# 03_-_HV_Input.net
KiCad netlist of a schematic drawn in Altium Designer
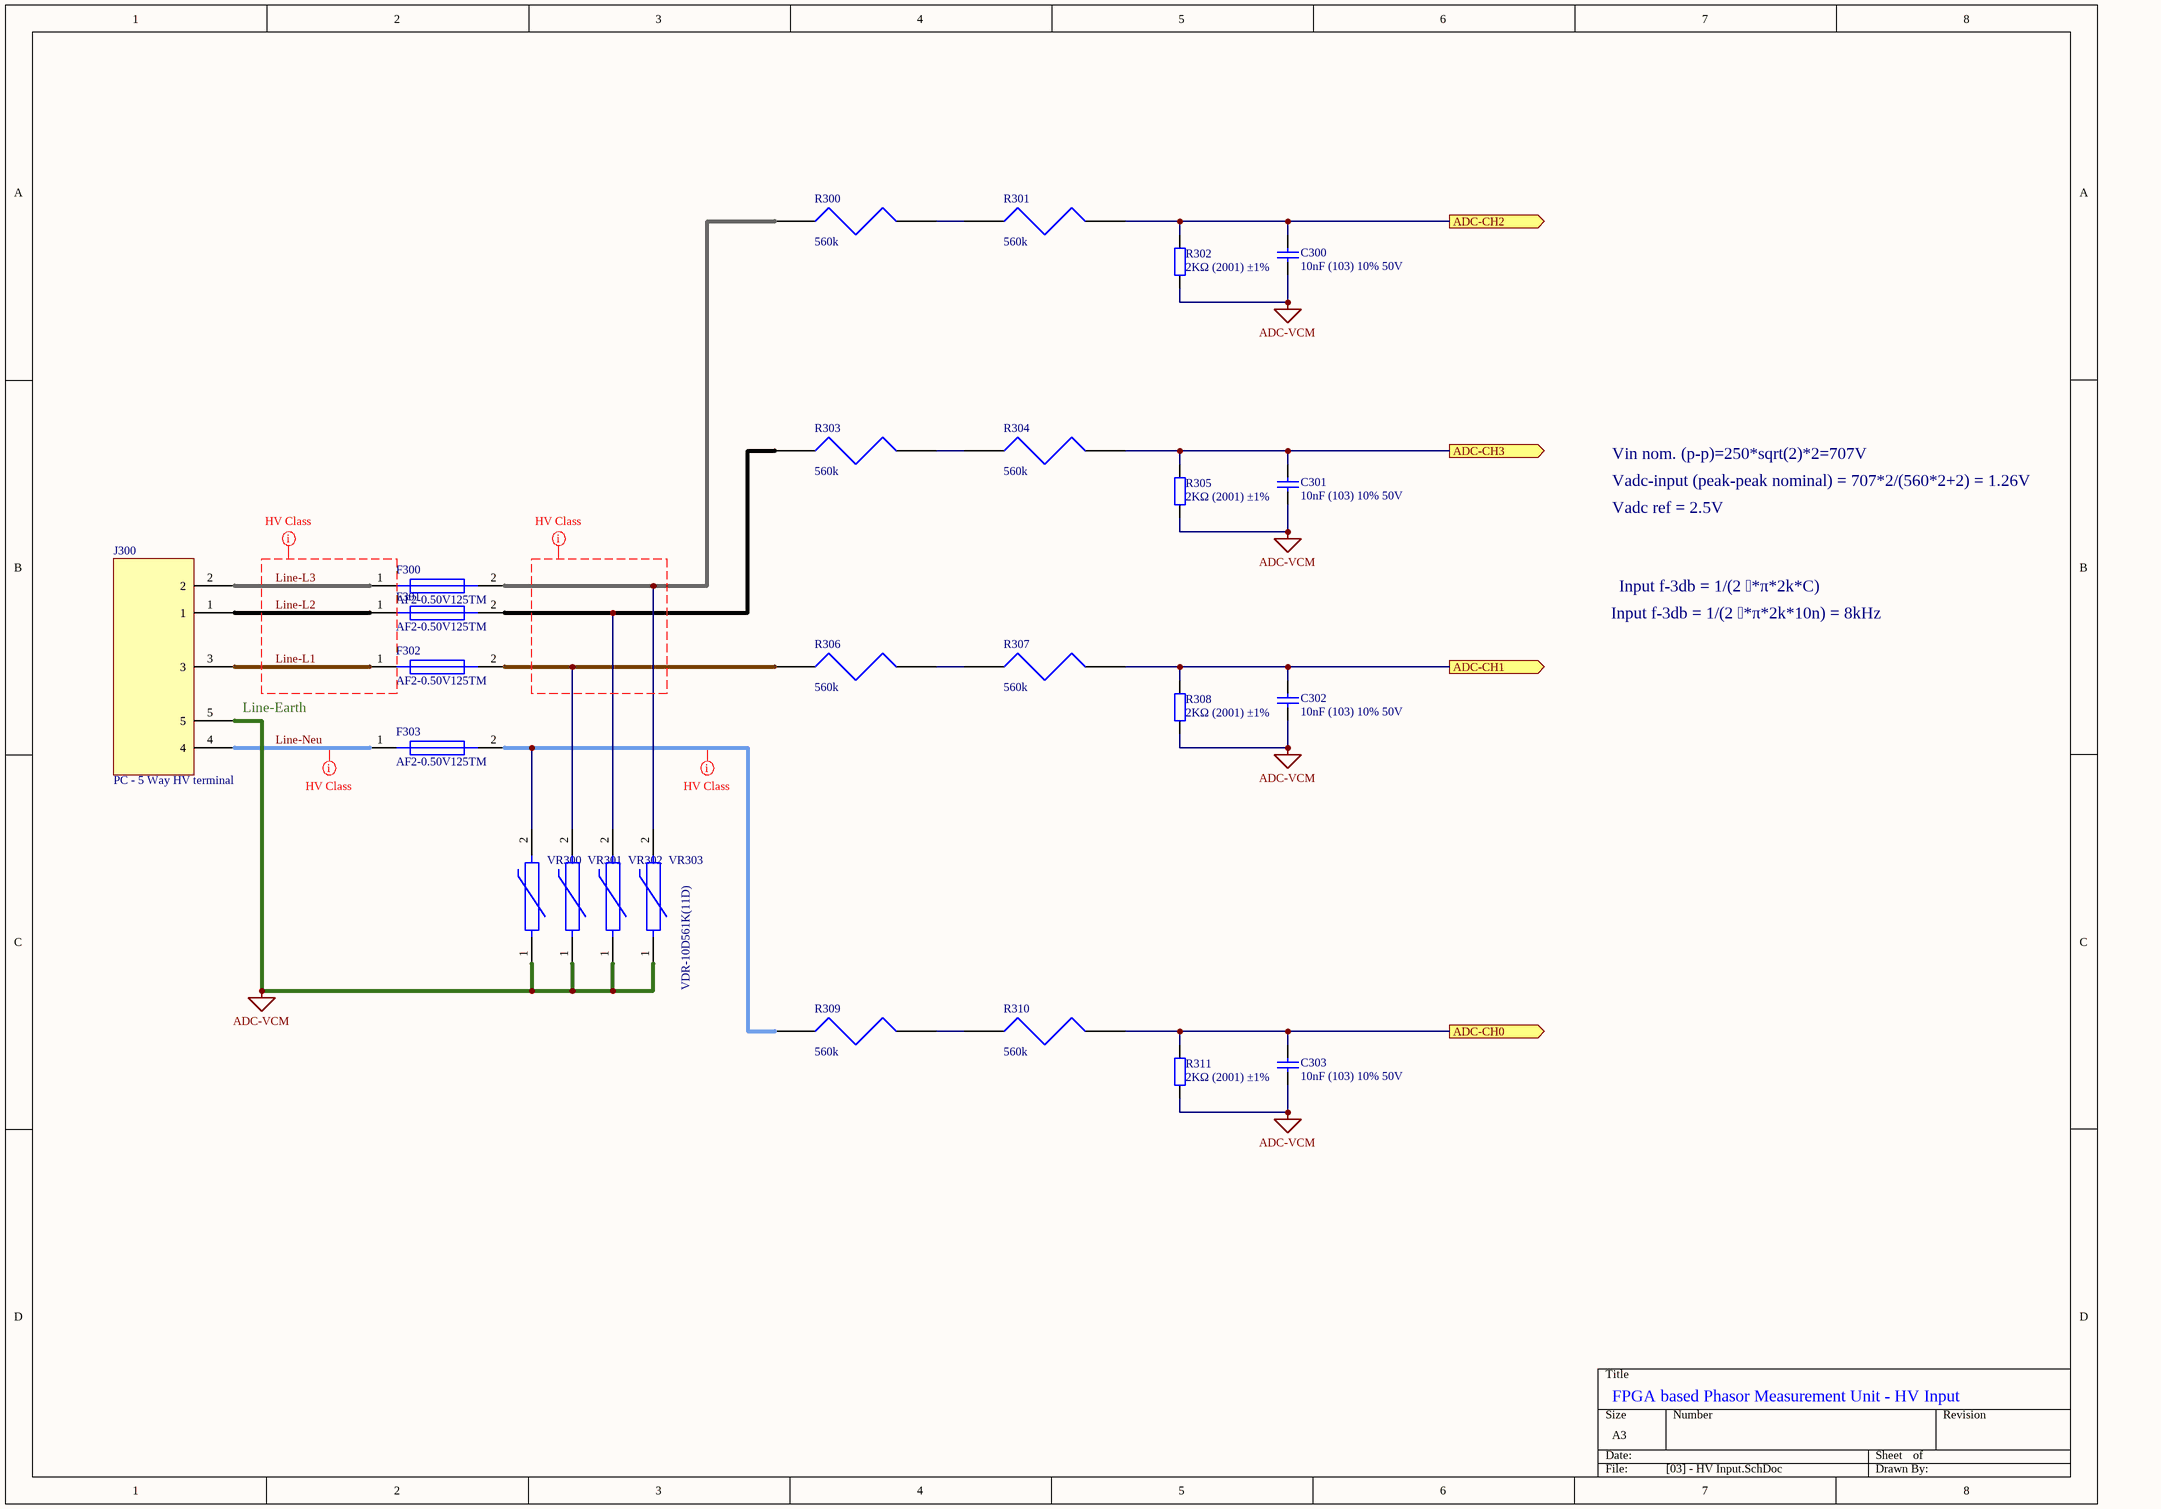
[diagram p0: [03] - HV Input.SchDoc]

(export (version "E")
  (design (tool "Eeschema 10.0.6"))
  (components
    (comp (ref "C300")
      (value "10nF (103) 10% 50V")
      (footprint "0805_C")
      (description "贴片电容")
      (libsource (lib "Cap") (part "0805 10nF (103) 10% 50V"))
    )
    (comp (ref "C301")
      (value "10nF (103) 10% 50V")
      (footprint "0805_C")
      (description "贴片电容")
      (libsource (lib "Cap") (part "0805 10nF (103) 10% 50V"))
    )
    (comp (ref "C302")
      (value "10nF (103) 10% 50V")
      (footprint "0805_C")
      (description "贴片电容")
      (libsource (lib "Cap") (part "0805 10nF (103) 10% 50V"))
    )
    (comp (ref "C303")
      (value "10nF (103) 10% 50V")
      (footprint "0805_C")
      (description "贴片电容")
      (libsource (lib "Cap") (part "0805 10nF (103) 10% 50V"))
    )
    (comp (ref "F300")
      (value "AF2-0.50V125TM")
      (footprint "2410 Fuse")
      (description "Chip Fuse Fast Blow 500mA 231mΩ 100A AC，50A DC 0.1 2410 Surface Mount Fuses RoHS")
      (libsource (lib "FPGA_PMU_lib") (part "AF2-0.50V125TM"))
    )
    (comp (ref "F301")
      (value "AF2-0.50V125TM")
      (footprint "2410 Fuse")
      (description "Chip Fuse Fast Blow 500mA 231mΩ 100A AC，50A DC 0.1 2410 Surface Mount Fuses RoHS")
      (libsource (lib "FPGA_PMU_lib") (part "AF2-0.50V125TM"))
    )
    (comp (ref "F302")
      (value "AF2-0.50V125TM")
      (footprint "2410 Fuse")
      (description "Chip Fuse Fast Blow 500mA 231mΩ 100A AC，50A DC 0.1 2410 Surface Mount Fuses RoHS")
      (libsource (lib "FPGA_PMU_lib") (part "AF2-0.50V125TM"))
    )
    (comp (ref "F303")
      (value "AF2-0.50V125TM")
      (footprint "2410 Fuse")
      (description "Chip Fuse Fast Blow 500mA 231mΩ 100A AC，50A DC 0.1 2410 Surface Mount Fuses RoHS")
      (libsource (lib "FPGA_PMU_lib") (part "AF2-0.50V125TM"))
    )
    (comp (ref "J300")
      (value "PC - 5 Way HV terminal")
      (footprint "1017517")
      (description "TDPT 4/ 5-SC-6,35-ZB - 1017517")
      (libsource (lib "FPGA_PMU_lib") (part "PC - 5 Way HV terminal"))
    )
    (comp (ref "R300")
      (value "560k")
      (footprint "FPGA_PMU_lib:2512_HV_RES")
      (description "HIGH VOLTAGE RESISTOR 560KOHMS ±1% 1W 2512 ROHS")
      (libsource (lib "FPGA_PMU_lib") (part "HR2512F560KE04Z"))
    )
    (comp (ref "R301")
      (value "560k")
      (footprint "FPGA_PMU_lib:2512_HV_RES")
      (description "HIGH VOLTAGE RESISTOR 560KOHMS ±1% 1W 2512 ROHS")
      (libsource (lib "FPGA_PMU_lib") (part "HR2512F560KE04Z"))
    )
    (comp (ref "R302")
      (value "2KΩ (2001) ±1%")
      (footprint "0805_R")
      (description "贴片电阻")
      (libsource (lib "RES") (part "0805 2KΩ (2001) 1%"))
    )
    (comp (ref "R303")
      (value "560k")
      (footprint "FPGA_PMU_lib:2512_HV_RES")
      (description "HIGH VOLTAGE RESISTOR 560KOHMS ±1% 1W 2512 ROHS")
      (libsource (lib "FPGA_PMU_lib") (part "HR2512F560KE04Z"))
    )
    (comp (ref "R304")
      (value "560k")
      (footprint "FPGA_PMU_lib:2512_HV_RES")
      (description "HIGH VOLTAGE RESISTOR 560KOHMS ±1% 1W 2512 ROHS")
      (libsource (lib "FPGA_PMU_lib") (part "HR2512F560KE04Z"))
    )
    (comp (ref "R305")
      (value "2KΩ (2001) ±1%")
      (footprint "0805_R")
      (description "贴片电阻")
      (libsource (lib "RES") (part "0805 2KΩ (2001) 1%"))
    )
    (comp (ref "R306")
      (value "560k")
      (footprint "FPGA_PMU_lib:2512_HV_RES")
      (description "HIGH VOLTAGE RESISTOR 560KOHMS ±1% 1W 2512 ROHS")
      (libsource (lib "FPGA_PMU_lib") (part "HR2512F560KE04Z"))
    )
    (comp (ref "R307")
      (value "560k")
      (footprint "FPGA_PMU_lib:2512_HV_RES")
      (description "HIGH VOLTAGE RESISTOR 560KOHMS ±1% 1W 2512 ROHS")
      (libsource (lib "FPGA_PMU_lib") (part "HR2512F560KE04Z"))
    )
    (comp (ref "R308")
      (value "2KΩ (2001) ±1%")
      (footprint "0805_R")
      (description "贴片电阻")
      (libsource (lib "RES") (part "0805 2KΩ (2001) 1%"))
    )
    (comp (ref "R309")
      (value "560k")
      (footprint "FPGA_PMU_lib:2512_HV_RES")
      (description "HIGH VOLTAGE RESISTOR 560KOHMS ±1% 1W 2512 ROHS")
      (libsource (lib "FPGA_PMU_lib") (part "HR2512F560KE04Z"))
    )
    (comp (ref "R310")
      (value "560k")
      (footprint "FPGA_PMU_lib:2512_HV_RES")
      (description "HIGH VOLTAGE RESISTOR 560KOHMS ±1% 1W 2512 ROHS")
      (libsource (lib "FPGA_PMU_lib") (part "HR2512F560KE04Z"))
    )
    (comp (ref "R311")
      (value "2KΩ (2001) ±1%")
      (footprint "0805_R")
      (description "贴片电阻")
      (libsource (lib "RES") (part "0805 2KΩ (2001) 1%"))
    )
    (comp (ref "VR300")
      (value "VDR-10D561K(11D)")
      (footprint "VDR-10D561K(11D)")
      (description "460V 920V 2.5KA 560V Through Hole Varistors RoHS")
      (libsource (lib "FPGA_PMU_lib") (part "VDR-10D561K(11D)"))
    )
    (comp (ref "VR301")
      (value "VDR-10D561K(11D)")
      (footprint "VDR-10D561K(11D)")
      (description "460V 920V 2.5KA 560V Through Hole Varistors RoHS")
      (libsource (lib "FPGA_PMU_lib") (part "VDR-10D561K(11D)"))
    )
    (comp (ref "VR302")
      (value "VDR-10D561K(11D)")
      (footprint "VDR-10D561K(11D)")
      (description "460V 920V 2.5KA 560V Through Hole Varistors RoHS")
      (libsource (lib "FPGA_PMU_lib") (part "VDR-10D561K(11D)"))
    )
    (comp (ref "VR303")
      (value "VDR-10D561K(11D)")
      (footprint "VDR-10D561K(11D)")
      (description "460V 920V 2.5KA 560V Through Hole Varistors RoHS")
      (libsource (lib "FPGA_PMU_lib") (part "VDR-10D561K(11D)"))
    )
  )
  (nets
    (net (code "1") (name "/ADC-CH0") (class "Default")
      (node (ref "C303") (pin "2") (pinfunction "2_2") (pintype "passive"))
      (node (ref "R310") (pin "2") (pinfunction "2_2") (pintype "passive"))
      (node (ref "R311") (pin "2") (pinfunction "2_2") (pintype "passive"))
    )
    (net (code "2") (name "/ADC-CH1") (class "Default")
      (node (ref "C302") (pin "2") (pinfunction "2_2") (pintype "passive"))
      (node (ref "R307") (pin "2") (pinfunction "2_2") (pintype "passive"))
      (node (ref "R308") (pin "2") (pinfunction "2_2") (pintype "passive"))
    )
    (net (code "3") (name "/ADC-CH2") (class "Default")
      (node (ref "C300") (pin "2") (pinfunction "2_2") (pintype "passive"))
      (node (ref "R301") (pin "2") (pinfunction "2_2") (pintype "passive"))
      (node (ref "R302") (pin "2") (pinfunction "2_2") (pintype "passive"))
    )
    (net (code "4") (name "/ADC-CH3") (class "Default")
      (node (ref "C301") (pin "2") (pinfunction "2_2") (pintype "passive"))
      (node (ref "R304") (pin "2") (pinfunction "2_2") (pintype "passive"))
      (node (ref "R305") (pin "2") (pinfunction "2_2") (pintype "passive"))
    )
    (net (code "5") (name "/Line-L1") (class "Default")
      (node (ref "F302") (pin "1") (pinfunction "1_1") (pintype "passive"))
      (node (ref "J300") (pin "3") (pinfunction "3_3") (pintype "passive"))
    )
    (net (code "6") (name "/Line-L2") (class "Default")
      (node (ref "F301") (pin "1") (pinfunction "1_1") (pintype "passive"))
      (node (ref "J300") (pin "1") (pinfunction "1_1") (pintype "passive"))
    )
    (net (code "7") (name "/Line-L3") (class "Default")
      (node (ref "F300") (pin "1") (pinfunction "1_1") (pintype "passive"))
      (node (ref "J300") (pin "2") (pinfunction "2_2") (pintype "passive"))
    )
    (net (code "8") (name "/Line-Neu") (class "Default")
      (node (ref "F303") (pin "1") (pinfunction "1_1") (pintype "passive"))
      (node (ref "J300") (pin "4") (pinfunction "4_4") (pintype "passive"))
    )
    (net (code "9") (name "ADC-VCM") (class "Default")
      (node (ref "C300") (pin "1") (pinfunction "1_1") (pintype "passive"))
      (node (ref "C301") (pin "1") (pinfunction "1_1") (pintype "passive"))
      (node (ref "C302") (pin "1") (pinfunction "1_1") (pintype "passive"))
      (node (ref "C303") (pin "1") (pinfunction "1_1") (pintype "passive"))
      (node (ref "J300") (pin "5") (pinfunction "5_5") (pintype "passive"))
      (node (ref "R302") (pin "1") (pinfunction "1_1") (pintype "passive"))
      (node (ref "R305") (pin "1") (pinfunction "1_1") (pintype "passive"))
      (node (ref "R308") (pin "1") (pinfunction "1_1") (pintype "passive"))
      (node (ref "R311") (pin "1") (pinfunction "1_1") (pintype "passive"))
      (node (ref "VR300") (pin "1") (pinfunction "1_1") (pintype "passive"))
      (node (ref "VR301") (pin "1") (pinfunction "1_1") (pintype "passive"))
      (node (ref "VR302") (pin "1") (pinfunction "1_1") (pintype "passive"))
      (node (ref "VR303") (pin "1") (pinfunction "1_1") (pintype "passive"))
    )
    (net (code "10") (name "Net-(F300-Pad2)") (class "Default")
      (node (ref "F300") (pin "2") (pinfunction "2_2") (pintype "passive"))
      (node (ref "R300") (pin "1") (pinfunction "1_1") (pintype "passive"))
      (node (ref "VR303") (pin "2") (pinfunction "2_2") (pintype "passive"))
    )
    (net (code "11") (name "Net-(F301-Pad2)") (class "Default")
      (node (ref "F301") (pin "2") (pinfunction "2_2") (pintype "passive"))
      (node (ref "R303") (pin "1") (pinfunction "1_1") (pintype "passive"))
      (node (ref "VR302") (pin "2") (pinfunction "2_2") (pintype "passive"))
    )
    (net (code "12") (name "Net-(F302-Pad2)") (class "Default")
      (node (ref "F302") (pin "2") (pinfunction "2_2") (pintype "passive"))
      (node (ref "R306") (pin "1") (pinfunction "1_1") (pintype "passive"))
      (node (ref "VR301") (pin "2") (pinfunction "2_2") (pintype "passive"))
    )
    (net (code "13") (name "Net-(F303-Pad2)") (class "Default")
      (node (ref "F303") (pin "2") (pinfunction "2_2") (pintype "passive"))
      (node (ref "R309") (pin "1") (pinfunction "1_1") (pintype "passive"))
      (node (ref "VR300") (pin "2") (pinfunction "2_2") (pintype "passive"))
    )
    (net (code "14") (name "Net-(R300-Pad2)") (class "Default")
      (node (ref "R300") (pin "2") (pinfunction "2_2") (pintype "passive"))
      (node (ref "R301") (pin "1") (pinfunction "1_1") (pintype "passive"))
    )
    (net (code "15") (name "Net-(R303-Pad2)") (class "Default")
      (node (ref "R303") (pin "2") (pinfunction "2_2") (pintype "passive"))
      (node (ref "R304") (pin "1") (pinfunction "1_1") (pintype "passive"))
    )
    (net (code "16") (name "Net-(R306-Pad2)") (class "Default")
      (node (ref "R306") (pin "2") (pinfunction "2_2") (pintype "passive"))
      (node (ref "R307") (pin "1") (pinfunction "1_1") (pintype "passive"))
    )
    (net (code "17") (name "Net-(R309-Pad2)") (class "Default")
      (node (ref "R309") (pin "2") (pinfunction "2_2") (pintype "passive"))
      (node (ref "R310") (pin "1") (pinfunction "1_1") (pintype "passive"))
    )
  )
)
